# Sheet3.net
KiCad netlist of a schematic drawn in Altium Designer
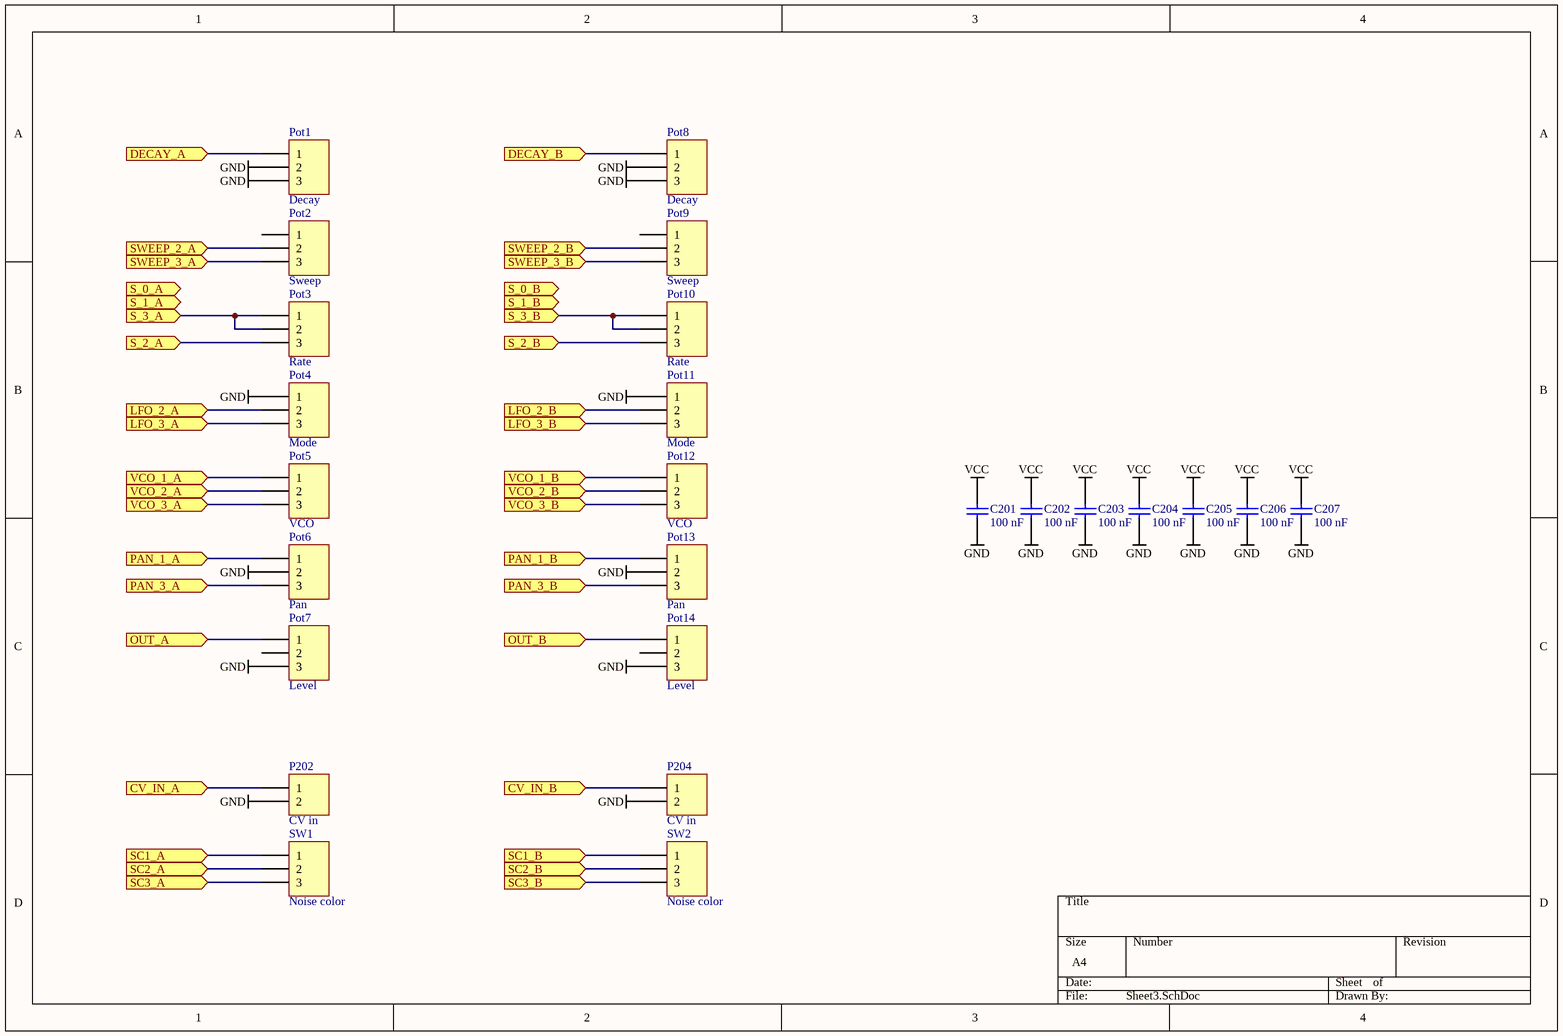
[diagram p0: Sheet3.SchDoc]

(export (version "E")
  (design (tool "Eeschema 10.0.6"))
  (components
    (comp (ref "C201")
      (value "100 nF")
      (footprint "C1206")
      (description "Capacitor")
      (fields (field (name "Comment") "Cap") (field (name "PUBLISHER") "Altium Limited"))
      (libsource (lib "Miscellaneous Devices") (part "Cap"))
    )
    (comp (ref "C202")
      (value "100 nF")
      (footprint "C1206")
      (description "Capacitor")
      (fields (field (name "Comment") "Cap") (field (name "PUBLISHER") "Altium Limited"))
      (libsource (lib "Miscellaneous Devices") (part "Cap"))
    )
    (comp (ref "C203")
      (value "100 nF")
      (footprint "C1206")
      (description "Capacitor")
      (fields (field (name "Comment") "Cap") (field (name "PUBLISHER") "Altium Limited"))
      (libsource (lib "Miscellaneous Devices") (part "Cap"))
    )
    (comp (ref "C204")
      (value "100 nF")
      (footprint "C1206")
      (description "Capacitor")
      (fields (field (name "Comment") "Cap") (field (name "PUBLISHER") "Altium Limited"))
      (libsource (lib "Miscellaneous Devices") (part "Cap"))
    )
    (comp (ref "C205")
      (value "100 nF")
      (footprint "C1206")
      (description "Capacitor")
      (fields (field (name "Comment") "Cap") (field (name "PUBLISHER") "Altium Limited"))
      (libsource (lib "Miscellaneous Devices") (part "Cap"))
    )
    (comp (ref "C206")
      (value "100 nF")
      (footprint "C1206")
      (description "Capacitor")
      (fields (field (name "Comment") "Cap") (field (name "PUBLISHER") "Altium Limited"))
      (libsource (lib "Miscellaneous Devices") (part "Cap"))
    )
    (comp (ref "C207")
      (value "100 nF")
      (footprint "C1206")
      (description "Capacitor")
      (fields (field (name "Comment") "Cap") (field (name "PUBLISHER") "Altium Limited"))
      (libsource (lib "Miscellaneous Devices") (part "Cap"))
    )
    (comp (ref "P202")
      (value "CV in")
      (footprint "HDR1X2")
      (description "Header, 2-Pin")
      (fields (field (name "PUBLISHER") "Altium Limited"))
      (libsource (lib "Miscellaneous Connectors") (part "Header 2"))
    )
    (comp (ref "P204")
      (value "CV in")
      (footprint "HDR1X2")
      (description "Header, 2-Pin")
      (fields (field (name "PUBLISHER") "Altium Limited"))
      (libsource (lib "Miscellaneous Connectors") (part "Header 2"))
    )
    (comp (ref "Pot1")
      (value "Decay")
      (footprint "HDR1X3")
      (description "Header, 3-Pin")
      (fields (field (name "PUBLISHER") "Altium Limited"))
      (libsource (lib "Miscellaneous Connectors") (part "Header 3"))
    )
    (comp (ref "Pot2")
      (value "Sweep")
      (footprint "HDR1X3")
      (description "Header, 3-Pin")
      (fields (field (name "PUBLISHER") "Altium Limited"))
      (libsource (lib "Miscellaneous Connectors") (part "Header 3"))
    )
    (comp (ref "Pot3")
      (value "Rate")
      (footprint "HDR1X3")
      (description "Header, 3-Pin")
      (fields (field (name "PUBLISHER") "Altium Limited"))
      (libsource (lib "Miscellaneous Connectors") (part "Header 3"))
    )
    (comp (ref "Pot4")
      (value "Mode")
      (footprint "HDR1X3")
      (description "Header, 3-Pin")
      (fields (field (name "PUBLISHER") "Altium Limited"))
      (libsource (lib "Miscellaneous Connectors") (part "Header 3"))
    )
    (comp (ref "Pot5")
      (value "VCO")
      (footprint "HDR1X3")
      (description "Header, 3-Pin")
      (fields (field (name "PUBLISHER") "Altium Limited"))
      (libsource (lib "Miscellaneous Connectors") (part "Header 3"))
    )
    (comp (ref "Pot6")
      (value "Pan")
      (footprint "HDR1X3")
      (description "Header, 3-Pin")
      (fields (field (name "PUBLISHER") "Altium Limited"))
      (libsource (lib "Miscellaneous Connectors") (part "Header 3"))
    )
    (comp (ref "Pot7")
      (value "Level")
      (footprint "HDR1X3")
      (description "Header, 3-Pin")
      (fields (field (name "PUBLISHER") "Altium Limited"))
      (libsource (lib "Miscellaneous Connectors") (part "Header 3"))
    )
    (comp (ref "Pot8")
      (value "Decay")
      (footprint "HDR1X3")
      (description "Header, 3-Pin")
      (fields (field (name "PUBLISHER") "Altium Limited"))
      (libsource (lib "Miscellaneous Connectors") (part "Header 3"))
    )
    (comp (ref "Pot9")
      (value "Sweep")
      (footprint "HDR1X3")
      (description "Header, 3-Pin")
      (fields (field (name "PUBLISHER") "Altium Limited"))
      (libsource (lib "Miscellaneous Connectors") (part "Header 3"))
    )
    (comp (ref "Pot10")
      (value "Rate")
      (footprint "HDR1X3")
      (description "Header, 3-Pin")
      (fields (field (name "PUBLISHER") "Altium Limited"))
      (libsource (lib "Miscellaneous Connectors") (part "Header 3"))
    )
    (comp (ref "Pot11")
      (value "Mode")
      (footprint "HDR1X3")
      (description "Header, 3-Pin")
      (fields (field (name "PUBLISHER") "Altium Limited"))
      (libsource (lib "Miscellaneous Connectors") (part "Header 3"))
    )
    (comp (ref "Pot12")
      (value "VCO")
      (footprint "HDR1X3")
      (description "Header, 3-Pin")
      (fields (field (name "PUBLISHER") "Altium Limited"))
      (libsource (lib "Miscellaneous Connectors") (part "Header 3"))
    )
    (comp (ref "Pot13")
      (value "Pan")
      (footprint "HDR1X3")
      (description "Header, 3-Pin")
      (fields (field (name "PUBLISHER") "Altium Limited"))
      (libsource (lib "Miscellaneous Connectors") (part "Header 3"))
    )
    (comp (ref "Pot14")
      (value "Level")
      (footprint "HDR1X3")
      (description "Header, 3-Pin")
      (fields (field (name "PUBLISHER") "Altium Limited"))
      (libsource (lib "Miscellaneous Connectors") (part "Header 3"))
    )
    (comp (ref "SW1")
      (value "Noise color")
      (footprint "HDR1X3")
      (description "Header, 3-Pin")
      (fields (field (name "PUBLISHER") "Altium Limited"))
      (libsource (lib "Miscellaneous Connectors") (part "Header 3"))
    )
    (comp (ref "SW2")
      (value "Noise color")
      (footprint "HDR1X3")
      (description "Header, 3-Pin")
      (fields (field (name "PUBLISHER") "Altium Limited"))
      (libsource (lib "Miscellaneous Connectors") (part "Header 3"))
    )
  )
  (nets
    (net (code "1") (name "/CV_IN_A") (class "Default")
      (node (ref "P202") (pin "1") (pinfunction "1_1") (pintype "passive"))
    )
    (net (code "2") (name "/CV_IN_B") (class "Default")
      (node (ref "P204") (pin "1") (pinfunction "1_1") (pintype "passive"))
    )
    (net (code "3") (name "/DECAY_A") (class "Default")
      (node (ref "Pot1") (pin "1") (pinfunction "1_1") (pintype "passive"))
    )
    (net (code "4") (name "/DECAY_B") (class "Default")
      (node (ref "Pot8") (pin "1") (pinfunction "1_1") (pintype "passive"))
    )
    (net (code "5") (name "/LFO_2_A") (class "Default")
      (node (ref "Pot4") (pin "2") (pinfunction "2_2") (pintype "passive"))
    )
    (net (code "6") (name "/LFO_2_B") (class "Default")
      (node (ref "Pot11") (pin "2") (pinfunction "2_2") (pintype "passive"))
    )
    (net (code "7") (name "/LFO_3_A") (class "Default")
      (node (ref "Pot4") (pin "3") (pinfunction "3_3") (pintype "passive"))
    )
    (net (code "8") (name "/LFO_3_B") (class "Default")
      (node (ref "Pot11") (pin "3") (pinfunction "3_3") (pintype "passive"))
    )
    (net (code "9") (name "/OUT_A") (class "Default")
      (node (ref "Pot7") (pin "1") (pinfunction "1_1") (pintype "passive"))
    )
    (net (code "10") (name "/OUT_B") (class "Default")
      (node (ref "Pot14") (pin "1") (pinfunction "1_1") (pintype "passive"))
    )
    (net (code "11") (name "/PAN_1_A") (class "Default")
      (node (ref "Pot6") (pin "1") (pinfunction "1_1") (pintype "passive"))
    )
    (net (code "12") (name "/PAN_1_B") (class "Default")
      (node (ref "Pot13") (pin "1") (pinfunction "1_1") (pintype "passive"))
    )
    (net (code "13") (name "/PAN_3_A") (class "Default")
      (node (ref "Pot6") (pin "3") (pinfunction "3_3") (pintype "passive"))
    )
    (net (code "14") (name "/PAN_3_B") (class "Default")
      (node (ref "Pot13") (pin "3") (pinfunction "3_3") (pintype "passive"))
    )
    (net (code "15") (name "/SC1_A") (class "Default")
      (node (ref "SW1") (pin "1") (pinfunction "1_1") (pintype "passive"))
    )
    (net (code "16") (name "/SC1_B") (class "Default")
      (node (ref "SW2") (pin "1") (pinfunction "1_1") (pintype "passive"))
    )
    (net (code "17") (name "/SC2_A") (class "Default")
      (node (ref "SW1") (pin "2") (pinfunction "2_2") (pintype "passive"))
    )
    (net (code "18") (name "/SC2_B") (class "Default")
      (node (ref "SW2") (pin "2") (pinfunction "2_2") (pintype "passive"))
    )
    (net (code "19") (name "/SC3_A") (class "Default")
      (node (ref "SW1") (pin "3") (pinfunction "3_3") (pintype "passive"))
    )
    (net (code "20") (name "/SC3_B") (class "Default")
      (node (ref "SW2") (pin "3") (pinfunction "3_3") (pintype "passive"))
    )
    (net (code "21") (name "/SWEEP_2_A") (class "Default")
      (node (ref "Pot2") (pin "2") (pinfunction "2_2") (pintype "passive"))
    )
    (net (code "22") (name "/SWEEP_2_B") (class "Default")
      (node (ref "Pot9") (pin "2") (pinfunction "2_2") (pintype "passive"))
    )
    (net (code "23") (name "/SWEEP_3_A") (class "Default")
      (node (ref "Pot2") (pin "3") (pinfunction "3_3") (pintype "passive"))
    )
    (net (code "24") (name "/SWEEP_3_B") (class "Default")
      (node (ref "Pot9") (pin "3") (pinfunction "3_3") (pintype "passive"))
    )
    (net (code "29") (name "/S_2_A") (class "Default")
      (node (ref "Pot3") (pin "3") (pinfunction "3_3") (pintype "passive"))
    )
    (net (code "30") (name "/S_2_B") (class "Default")
      (node (ref "Pot10") (pin "3") (pinfunction "3_3") (pintype "passive"))
    )
    (net (code "31") (name "/S_3_A") (class "Default")
      (node (ref "Pot3") (pin "1") (pinfunction "1_1") (pintype "passive"))
      (node (ref "Pot3") (pin "2") (pinfunction "2_2") (pintype "passive"))
    )
    (net (code "32") (name "/S_3_B") (class "Default")
      (node (ref "Pot10") (pin "1") (pinfunction "1_1") (pintype "passive"))
      (node (ref "Pot10") (pin "2") (pinfunction "2_2") (pintype "passive"))
    )
    (net (code "33") (name "/VCO_1_A") (class "Default")
      (node (ref "Pot5") (pin "1") (pinfunction "1_1") (pintype "passive"))
    )
    (net (code "34") (name "/VCO_1_B") (class "Default")
      (node (ref "Pot12") (pin "1") (pinfunction "1_1") (pintype "passive"))
    )
    (net (code "35") (name "/VCO_2_A") (class "Default")
      (node (ref "Pot5") (pin "2") (pinfunction "2_2") (pintype "passive"))
    )
    (net (code "36") (name "/VCO_2_B") (class "Default")
      (node (ref "Pot12") (pin "2") (pinfunction "2_2") (pintype "passive"))
    )
    (net (code "37") (name "/VCO_3_A") (class "Default")
      (node (ref "Pot5") (pin "3") (pinfunction "3_3") (pintype "passive"))
    )
    (net (code "38") (name "/VCO_3_B") (class "Default")
      (node (ref "Pot12") (pin "3") (pinfunction "3_3") (pintype "passive"))
    )
    (net (code "39") (name "GND") (class "Default")
      (node (ref "C201") (pin "2") (pinfunction "2_2") (pintype "passive"))
      (node (ref "C202") (pin "2") (pinfunction "2_2") (pintype "passive"))
      (node (ref "C203") (pin "2") (pinfunction "2_2") (pintype "passive"))
      (node (ref "C204") (pin "2") (pinfunction "2_2") (pintype "passive"))
      (node (ref "C205") (pin "2") (pinfunction "2_2") (pintype "passive"))
      (node (ref "C206") (pin "2") (pinfunction "2_2") (pintype "passive"))
      (node (ref "C207") (pin "2") (pinfunction "2_2") (pintype "passive"))
      (node (ref "P202") (pin "2") (pinfunction "2_2") (pintype "passive"))
      (node (ref "P204") (pin "2") (pinfunction "2_2") (pintype "passive"))
      (node (ref "Pot1") (pin "2") (pinfunction "2_2") (pintype "passive"))
      (node (ref "Pot1") (pin "3") (pinfunction "3_3") (pintype "passive"))
      (node (ref "Pot11") (pin "1") (pinfunction "1_1") (pintype "passive"))
      (node (ref "Pot13") (pin "2") (pinfunction "2_2") (pintype "passive"))
      (node (ref "Pot14") (pin "3") (pinfunction "3_3") (pintype "passive"))
      (node (ref "Pot4") (pin "1") (pinfunction "1_1") (pintype "passive"))
      (node (ref "Pot6") (pin "2") (pinfunction "2_2") (pintype "passive"))
      (node (ref "Pot7") (pin "3") (pinfunction "3_3") (pintype "passive"))
      (node (ref "Pot8") (pin "2") (pinfunction "2_2") (pintype "passive"))
      (node (ref "Pot8") (pin "3") (pinfunction "3_3") (pintype "passive"))
    )
    (net (code "40") (name "VCC") (class "Default")
      (node (ref "C201") (pin "1") (pinfunction "1_1") (pintype "passive"))
      (node (ref "C202") (pin "1") (pinfunction "1_1") (pintype "passive"))
      (node (ref "C203") (pin "1") (pinfunction "1_1") (pintype "passive"))
      (node (ref "C204") (pin "1") (pinfunction "1_1") (pintype "passive"))
      (node (ref "C205") (pin "1") (pinfunction "1_1") (pintype "passive"))
      (node (ref "C206") (pin "1") (pinfunction "1_1") (pintype "passive"))
      (node (ref "C207") (pin "1") (pinfunction "1_1") (pintype "passive"))
    )
    (net (code "41") (name "unconnected-(Pot2-Pad1)") (class "Default")
      (node (ref "Pot2") (pin "1") (pinfunction "1_1") (pintype "passive"))
    )
    (net (code "42") (name "unconnected-(Pot7-Pad2)") (class "Default")
      (node (ref "Pot7") (pin "2") (pinfunction "2_2") (pintype "passive"))
    )
    (net (code "43") (name "unconnected-(Pot9-Pad1)") (class "Default")
      (node (ref "Pot9") (pin "1") (pinfunction "1_1") (pintype "passive"))
    )
    (net (code "44") (name "unconnected-(Pot14-Pad2)") (class "Default")
      (node (ref "Pot14") (pin "2") (pinfunction "2_2") (pintype "passive"))
    )
  )
)
